# Mother_Board_Connectors.net
KiCad netlist of a schematic drawn in Altium Designer
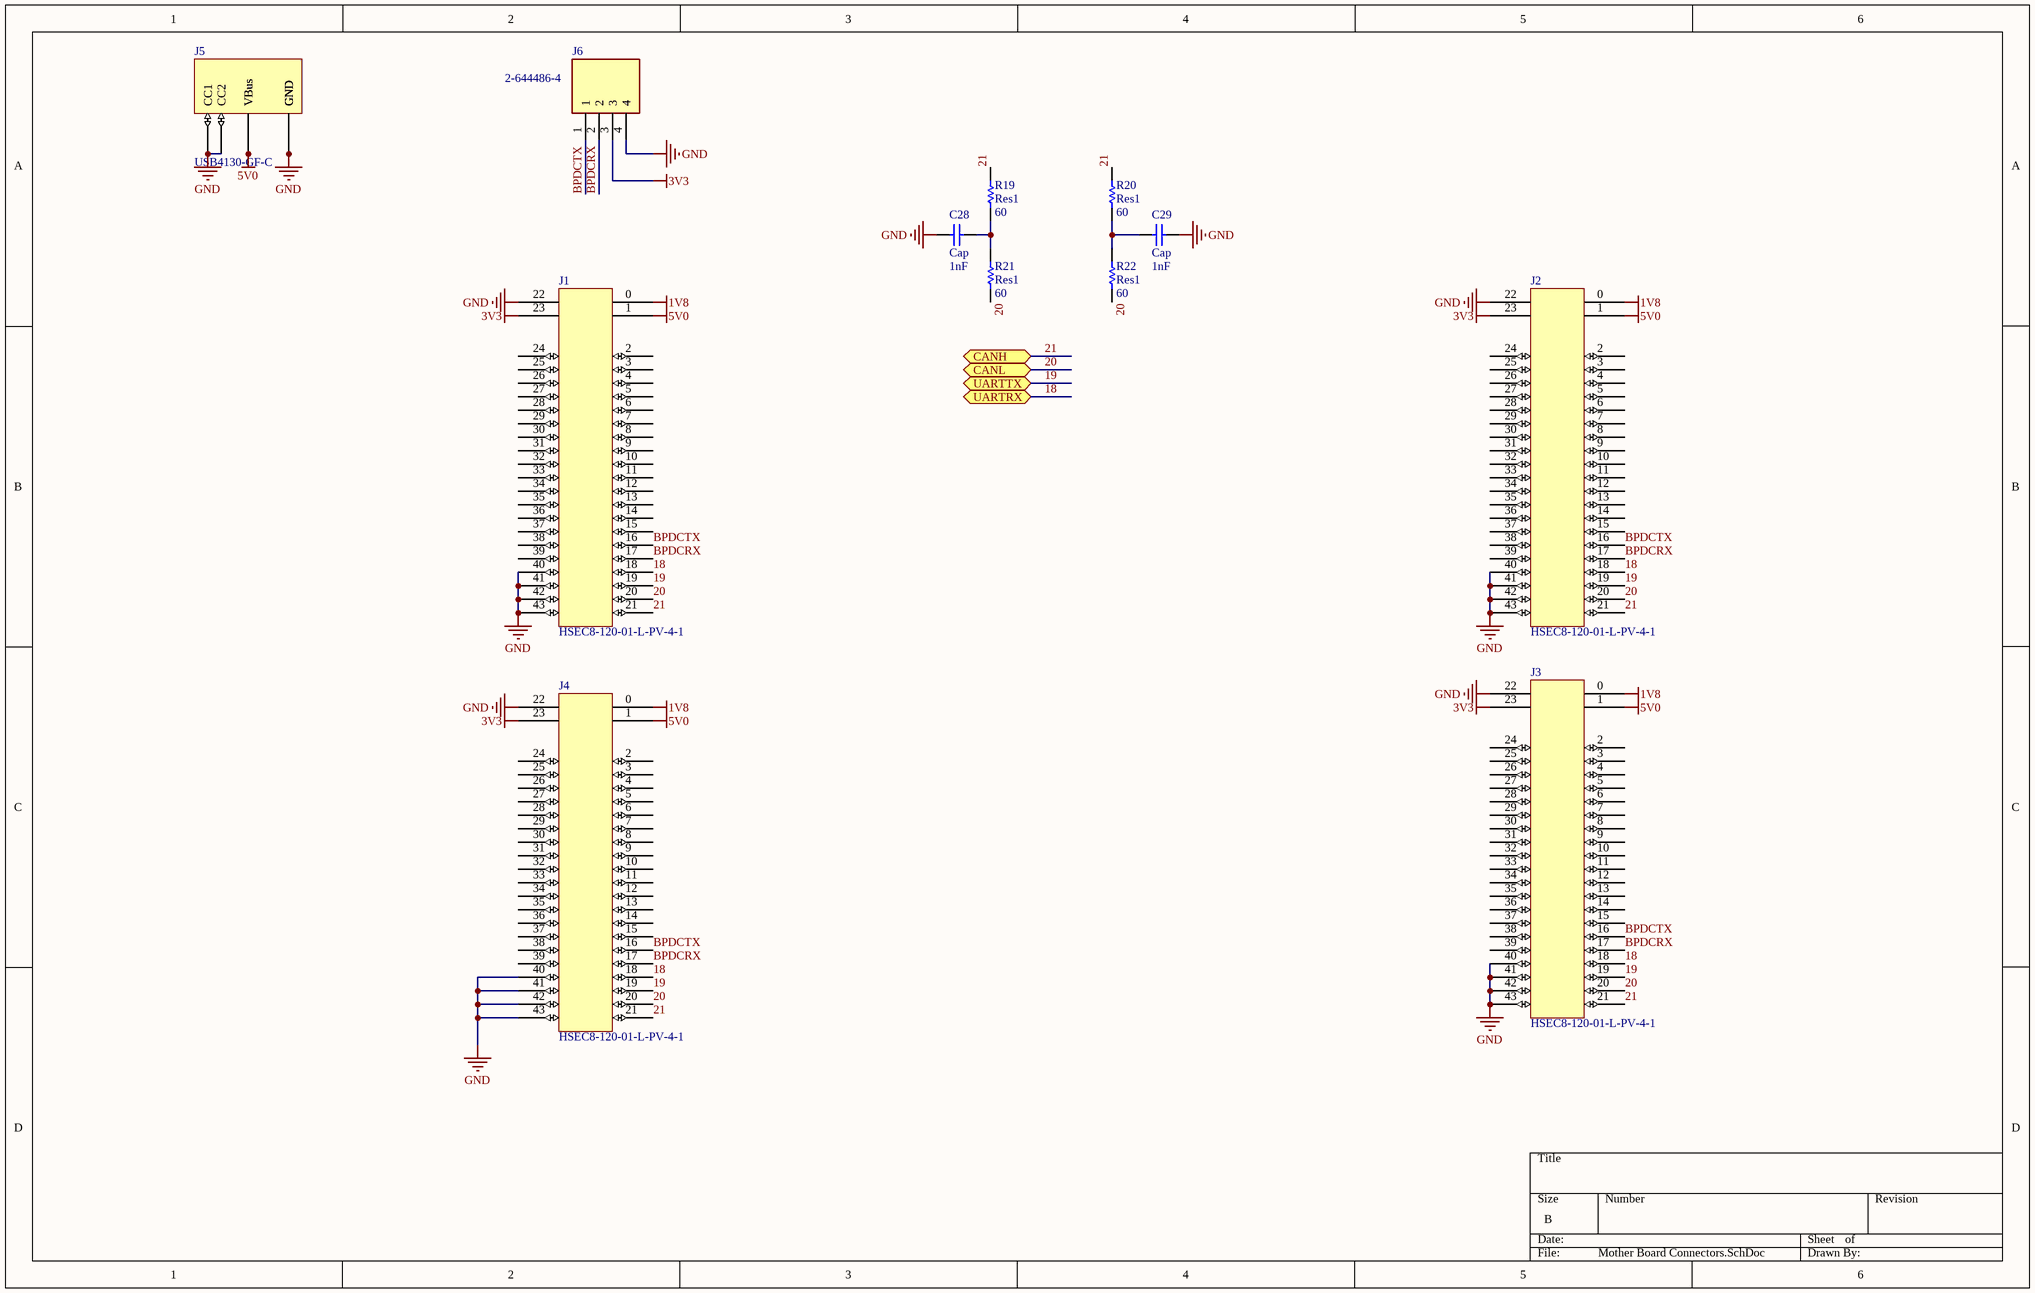
[diagram p0: Mother Board Connectors.SchDoc]

(export (version "E")
  (design (tool "Eeschema 10.0.6"))
  (components
    (comp (ref "C28")
      (value "Cap")
      (footprint "1608[0603]")
      (description "Capacitor")
      (fields (field (name "ALTIUM_VALUE") "1nF") (field (name "PUBLISHER") "Altium Limited"))
      (libsource (lib "Miscellaneous Devices") (part "Cap"))
    )
    (comp (ref "C29")
      (value "Cap")
      (footprint "1608[0603]")
      (description "Capacitor")
      (fields (field (name "ALTIUM_VALUE") "1nF") (field (name "PUBLISHER") "Altium Limited"))
      (libsource (lib "Miscellaneous Devices") (part "Cap"))
    )
    (comp (ref "J1")
      (value "HSEC8-120-01-L-PV-4-1")
      (footprint "HSEC8-120-01-L-PV-4-1")
      (libsource (lib "Edge Connector") (part "HSEC8-120-01-L-PV-4-1"))
    )
    (comp (ref "J2")
      (value "HSEC8-120-01-L-PV-4-1")
      (footprint "HSEC8-120-01-L-PV-4-1")
      (libsource (lib "Edge Connector") (part "HSEC8-120-01-L-PV-4-1"))
    )
    (comp (ref "J3")
      (value "HSEC8-120-01-L-PV-4-1")
      (footprint "HSEC8-120-01-L-PV-4-1")
      (libsource (lib "Edge Connector") (part "HSEC8-120-01-L-PV-4-1"))
    )
    (comp (ref "J4")
      (value "HSEC8-120-01-L-PV-4-1")
      (footprint "HSEC8-120-01-L-PV-4-1")
      (libsource (lib "Edge Connector") (part "HSEC8-120-01-L-PV-4-1"))
    )
    (comp (ref "J5")
      (value "USB4130-GF-C")
      (footprint "USB4130-GF-C")
      (libsource (lib "USB4130-GF-C") (part "USB4130-GF-C"))
    )
    (comp (ref "J6")
      (value "2-644486-4")
      (footprint "26444864")
      (description "Connector")
      (fields (field (name "MOUSER PART NUMBER") "571-2-644486-4"))
      (libsource (lib "SamacSys") (part "2-644486-4"))
    )
    (comp (ref "R19")
      (value "Res1")
      (footprint "0402-A")
      (description "Resistor")
      (fields (field (name "ALTIUM_VALUE") "60") (field (name "PUBLISHER") "Altium Limited"))
      (libsource (lib "Miscellaneous Devices") (part "Res1"))
    )
    (comp (ref "R20")
      (value "Res1")
      (footprint "0402-A")
      (description "Resistor")
      (fields (field (name "ALTIUM_VALUE") "60") (field (name "PUBLISHER") "Altium Limited"))
      (libsource (lib "Miscellaneous Devices") (part "Res1"))
    )
    (comp (ref "R21")
      (value "Res1")
      (footprint "0402-A")
      (description "Resistor")
      (fields (field (name "ALTIUM_VALUE") "60") (field (name "PUBLISHER") "Altium Limited"))
      (libsource (lib "Miscellaneous Devices") (part "Res1"))
    )
    (comp (ref "R22")
      (value "Res1")
      (footprint "0402-A")
      (description "Resistor")
      (fields (field (name "ALTIUM_VALUE") "60") (field (name "PUBLISHER") "Altium Limited"))
      (libsource (lib "Miscellaneous Devices") (part "Res1"))
    )
  )
  (nets
    (net (code "1") (name "/18") (class "Default")
      (node (ref "J1") (pin "18") (pinfunction "0_18") (pintype "bidirectional"))
      (node (ref "J2") (pin "18") (pinfunction "0_18") (pintype "bidirectional"))
      (node (ref "J3") (pin "18") (pinfunction "0_18") (pintype "bidirectional"))
      (node (ref "J4") (pin "18") (pinfunction "0_18") (pintype "bidirectional"))
    )
    (net (code "2") (name "/19") (class "Default")
      (node (ref "J1") (pin "19") (pinfunction "0_19") (pintype "bidirectional"))
      (node (ref "J2") (pin "19") (pinfunction "0_19") (pintype "bidirectional"))
      (node (ref "J3") (pin "19") (pinfunction "0_19") (pintype "bidirectional"))
      (node (ref "J4") (pin "19") (pinfunction "0_19") (pintype "bidirectional"))
    )
    (net (code "3") (name "/20") (class "Default")
      (node (ref "J1") (pin "20") (pinfunction "0_20") (pintype "bidirectional"))
      (node (ref "J2") (pin "20") (pinfunction "0_20") (pintype "bidirectional"))
      (node (ref "J3") (pin "20") (pinfunction "0_20") (pintype "bidirectional"))
      (node (ref "J4") (pin "20") (pinfunction "0_20") (pintype "bidirectional"))
      (node (ref "R21") (pin "1") (pinfunction "1_1") (pintype "passive"))
      (node (ref "R22") (pin "1") (pinfunction "1_1") (pintype "passive"))
    )
    (net (code "4") (name "/21") (class "Default")
      (node (ref "J1") (pin "21") (pinfunction "0_21") (pintype "bidirectional"))
      (node (ref "J2") (pin "21") (pinfunction "0_21") (pintype "bidirectional"))
      (node (ref "J3") (pin "21") (pinfunction "0_21") (pintype "bidirectional"))
      (node (ref "J4") (pin "21") (pinfunction "0_21") (pintype "bidirectional"))
      (node (ref "R19") (pin "2") (pinfunction "2_2") (pintype "passive"))
      (node (ref "R20") (pin "2") (pinfunction "2_2") (pintype "passive"))
    )
    (net (code "5") (name "/BPDCRX") (class "Default")
      (node (ref "J1") (pin "17") (pinfunction "0_17") (pintype "bidirectional"))
      (node (ref "J2") (pin "17") (pinfunction "0_17") (pintype "bidirectional"))
      (node (ref "J3") (pin "17") (pinfunction "0_17") (pintype "bidirectional"))
      (node (ref "J4") (pin "17") (pinfunction "0_17") (pintype "bidirectional"))
      (node (ref "J6") (pin "2") (pinfunction "2_2") (pintype "passive"))
    )
    (net (code "6") (name "/BPDCTX") (class "Default")
      (node (ref "J1") (pin "16") (pinfunction "0_16") (pintype "bidirectional"))
      (node (ref "J2") (pin "16") (pinfunction "0_16") (pintype "bidirectional"))
      (node (ref "J3") (pin "16") (pinfunction "0_16") (pintype "bidirectional"))
      (node (ref "J4") (pin "16") (pinfunction "0_16") (pintype "bidirectional"))
      (node (ref "J6") (pin "1") (pinfunction "1_1") (pintype "passive"))
    )
    (net (code "7") (name "1V8") (class "Default")
      (node (ref "J1") (pin "0") (pinfunction "0_0") (pintype "power_in"))
      (node (ref "J2") (pin "0") (pinfunction "0_0") (pintype "power_in"))
      (node (ref "J3") (pin "0") (pinfunction "0_0") (pintype "power_in"))
      (node (ref "J4") (pin "0") (pinfunction "0_0") (pintype "power_in"))
    )
    (net (code "8") (name "3V3") (class "Default")
      (node (ref "J1") (pin "23") (pinfunction "23_23") (pintype "power_in"))
      (node (ref "J2") (pin "23") (pinfunction "23_23") (pintype "power_in"))
      (node (ref "J3") (pin "23") (pinfunction "23_23") (pintype "power_in"))
      (node (ref "J4") (pin "23") (pinfunction "23_23") (pintype "power_in"))
      (node (ref "J6") (pin "3") (pinfunction "3_3") (pintype "passive"))
    )
    (net (code "9") (name "5V0") (class "Default")
      (node (ref "J1") (pin "1") (pinfunction "0_1") (pintype "power_in"))
      (node (ref "J2") (pin "1") (pinfunction "0_1") (pintype "power_in"))
      (node (ref "J3") (pin "1") (pinfunction "0_1") (pintype "power_in"))
      (node (ref "J4") (pin "1") (pinfunction "0_1") (pintype "power_in"))
      (node (ref "J5") (pin "2") (pinfunction "VBus_2") (pintype "power_in"))
      (node (ref "J5") (pin "5") (pinfunction "VBus_5") (pintype "power_in"))
    )
    (net (code "10") (name "GND") (class "Default")
      (node (ref "C28") (pin "2") (pinfunction "2_2") (pintype "passive"))
      (node (ref "C29") (pin "1") (pinfunction "1_1") (pintype "passive"))
      (node (ref "J1") (pin "22") (pinfunction "0_22") (pintype "power_in"))
      (node (ref "J1") (pin "40") (pinfunction "40_40") (pintype "bidirectional"))
      (node (ref "J1") (pin "41") (pinfunction "41_41") (pintype "bidirectional"))
      (node (ref "J1") (pin "42") (pinfunction "42_42") (pintype "bidirectional"))
      (node (ref "J1") (pin "43") (pinfunction "43_43") (pintype "bidirectional"))
      (node (ref "J2") (pin "22") (pinfunction "0_22") (pintype "power_in"))
      (node (ref "J2") (pin "40") (pinfunction "40_40") (pintype "bidirectional"))
      (node (ref "J2") (pin "41") (pinfunction "41_41") (pintype "bidirectional"))
      (node (ref "J2") (pin "42") (pinfunction "42_42") (pintype "bidirectional"))
      (node (ref "J2") (pin "43") (pinfunction "43_43") (pintype "bidirectional"))
      (node (ref "J3") (pin "22") (pinfunction "0_22") (pintype "power_in"))
      (node (ref "J3") (pin "40") (pinfunction "40_40") (pintype "bidirectional"))
      (node (ref "J3") (pin "41") (pinfunction "41_41") (pintype "bidirectional"))
      (node (ref "J3") (pin "42") (pinfunction "42_42") (pintype "bidirectional"))
      (node (ref "J3") (pin "43") (pinfunction "43_43") (pintype "bidirectional"))
      (node (ref "J4") (pin "22") (pinfunction "0_22") (pintype "power_in"))
      (node (ref "J4") (pin "40") (pinfunction "40_40") (pintype "bidirectional"))
      (node (ref "J4") (pin "41") (pinfunction "41_41") (pintype "bidirectional"))
      (node (ref "J4") (pin "42") (pinfunction "42_42") (pintype "bidirectional"))
      (node (ref "J4") (pin "43") (pinfunction "43_43") (pintype "bidirectional"))
      (node (ref "J5") (pin "1") (pinfunction "GND_1") (pintype "power_in"))
      (node (ref "J5") (pin "3") (pinfunction "CC1_3") (pintype "bidirectional"))
      (node (ref "J5") (pin "4") (pinfunction "CC2_4") (pintype "bidirectional"))
      (node (ref "J5") (pin "6") (pinfunction "GND_6") (pintype "power_in"))
      (node (ref "J5") (pin "7") (pinfunction "GND_7") (pintype "power_in"))
      (node (ref "J5") (pin "8") (pinfunction "GND_8") (pintype "power_in"))
      (node (ref "J6") (pin "4") (pinfunction "4_4") (pintype "passive"))
    )
    (net (code "11") (name "Net-(C28-Pad1)") (class "Default")
      (node (ref "C28") (pin "1") (pinfunction "1_1") (pintype "passive"))
      (node (ref "R19") (pin "1") (pinfunction "1_1") (pintype "passive"))
      (node (ref "R21") (pin "2") (pinfunction "2_2") (pintype "passive"))
    )
    (net (code "12") (name "Net-(C29-Pad2)") (class "Default")
      (node (ref "C29") (pin "2") (pinfunction "2_2") (pintype "passive"))
      (node (ref "R20") (pin "1") (pinfunction "1_1") (pintype "passive"))
      (node (ref "R22") (pin "2") (pinfunction "2_2") (pintype "passive"))
    )
    (net (code "13") (name "unconnected-(J1-0-Pad2)") (class "Default")
      (node (ref "J1") (pin "2") (pinfunction "0_2") (pintype "bidirectional"))
    )
    (net (code "14") (name "unconnected-(J1-0-Pad3)") (class "Default")
      (node (ref "J1") (pin "3") (pinfunction "0_3") (pintype "bidirectional"))
    )
    (net (code "15") (name "unconnected-(J1-0-Pad4)") (class "Default")
      (node (ref "J1") (pin "4") (pinfunction "0_4") (pintype "bidirectional"))
    )
    (net (code "16") (name "unconnected-(J1-0-Pad5)") (class "Default")
      (node (ref "J1") (pin "5") (pinfunction "0_5") (pintype "bidirectional"))
    )
    (net (code "17") (name "unconnected-(J1-0-Pad6)") (class "Default")
      (node (ref "J1") (pin "6") (pinfunction "0_6") (pintype "bidirectional"))
    )
    (net (code "18") (name "unconnected-(J1-0-Pad7)") (class "Default")
      (node (ref "J1") (pin "7") (pinfunction "0_7") (pintype "bidirectional"))
    )
    (net (code "19") (name "unconnected-(J1-0-Pad8)") (class "Default")
      (node (ref "J1") (pin "8") (pinfunction "0_8") (pintype "bidirectional"))
    )
    (net (code "20") (name "unconnected-(J1-0-Pad9)") (class "Default")
      (node (ref "J1") (pin "9") (pinfunction "0_9") (pintype "bidirectional"))
    )
    (net (code "21") (name "unconnected-(J1-0-Pad10)") (class "Default")
      (node (ref "J1") (pin "10") (pinfunction "0_10") (pintype "bidirectional"))
    )
    (net (code "22") (name "unconnected-(J1-0-Pad11)") (class "Default")
      (node (ref "J1") (pin "11") (pinfunction "0_11") (pintype "bidirectional"))
    )
    (net (code "23") (name "unconnected-(J1-0-Pad12)") (class "Default")
      (node (ref "J1") (pin "12") (pinfunction "0_12") (pintype "bidirectional"))
    )
    (net (code "24") (name "unconnected-(J1-0-Pad13)") (class "Default")
      (node (ref "J1") (pin "13") (pinfunction "0_13") (pintype "bidirectional"))
    )
    (net (code "25") (name "unconnected-(J1-0-Pad14)") (class "Default")
      (node (ref "J1") (pin "14") (pinfunction "0_14") (pintype "bidirectional"))
    )
    (net (code "26") (name "unconnected-(J1-0-Pad15)") (class "Default")
      (node (ref "J1") (pin "15") (pinfunction "0_15") (pintype "bidirectional"))
    )
    (net (code "27") (name "unconnected-(J1-Pad24)") (class "Default")
      (node (ref "J1") (pin "24") (pinfunction "24_24") (pintype "bidirectional"))
    )
    (net (code "28") (name "unconnected-(J1-Pad25)") (class "Default")
      (node (ref "J1") (pin "25") (pinfunction "25_25") (pintype "bidirectional"))
    )
    (net (code "29") (name "unconnected-(J1-Pad26)") (class "Default")
      (node (ref "J1") (pin "26") (pinfunction "26_26") (pintype "bidirectional"))
    )
    (net (code "30") (name "unconnected-(J1-Pad27)") (class "Default")
      (node (ref "J1") (pin "27") (pinfunction "27_27") (pintype "bidirectional"))
    )
    (net (code "31") (name "unconnected-(J1-Pad28)") (class "Default")
      (node (ref "J1") (pin "28") (pinfunction "28_28") (pintype "bidirectional"))
    )
    (net (code "32") (name "unconnected-(J1-Pad29)") (class "Default")
      (node (ref "J1") (pin "29") (pinfunction "29_29") (pintype "bidirectional"))
    )
    (net (code "33") (name "unconnected-(J1-Pad30)") (class "Default")
      (node (ref "J1") (pin "30") (pinfunction "30_30") (pintype "bidirectional"))
    )
    (net (code "34") (name "unconnected-(J1-Pad31)") (class "Default")
      (node (ref "J1") (pin "31") (pinfunction "31_31") (pintype "bidirectional"))
    )
    (net (code "35") (name "unconnected-(J1-Pad32)") (class "Default")
      (node (ref "J1") (pin "32") (pinfunction "32_32") (pintype "bidirectional"))
    )
    (net (code "36") (name "unconnected-(J1-Pad33)") (class "Default")
      (node (ref "J1") (pin "33") (pinfunction "33_33") (pintype "bidirectional"))
    )
    (net (code "37") (name "unconnected-(J1-Pad34)") (class "Default")
      (node (ref "J1") (pin "34") (pinfunction "34_34") (pintype "bidirectional"))
    )
    (net (code "38") (name "unconnected-(J1-Pad35)") (class "Default")
      (node (ref "J1") (pin "35") (pinfunction "35_35") (pintype "bidirectional"))
    )
    (net (code "39") (name "unconnected-(J1-Pad36)") (class "Default")
      (node (ref "J1") (pin "36") (pinfunction "36_36") (pintype "bidirectional"))
    )
    (net (code "40") (name "unconnected-(J1-Pad37)") (class "Default")
      (node (ref "J1") (pin "37") (pinfunction "37_37") (pintype "bidirectional"))
    )
    (net (code "41") (name "unconnected-(J1-Pad38)") (class "Default")
      (node (ref "J1") (pin "38") (pinfunction "38_38") (pintype "bidirectional"))
    )
    (net (code "42") (name "unconnected-(J1-Pad39)") (class "Default")
      (node (ref "J1") (pin "39") (pinfunction "39_39") (pintype "bidirectional"))
    )
    (net (code "43") (name "unconnected-(J2-0-Pad2)") (class "Default")
      (node (ref "J2") (pin "2") (pinfunction "0_2") (pintype "bidirectional"))
    )
    (net (code "44") (name "unconnected-(J2-0-Pad3)") (class "Default")
      (node (ref "J2") (pin "3") (pinfunction "0_3") (pintype "bidirectional"))
    )
    (net (code "45") (name "unconnected-(J2-0-Pad4)") (class "Default")
      (node (ref "J2") (pin "4") (pinfunction "0_4") (pintype "bidirectional"))
    )
    (net (code "46") (name "unconnected-(J2-0-Pad5)") (class "Default")
      (node (ref "J2") (pin "5") (pinfunction "0_5") (pintype "bidirectional"))
    )
    (net (code "47") (name "unconnected-(J2-0-Pad6)") (class "Default")
      (node (ref "J2") (pin "6") (pinfunction "0_6") (pintype "bidirectional"))
    )
    (net (code "48") (name "unconnected-(J2-0-Pad7)") (class "Default")
      (node (ref "J2") (pin "7") (pinfunction "0_7") (pintype "bidirectional"))
    )
    (net (code "49") (name "unconnected-(J2-0-Pad8)") (class "Default")
      (node (ref "J2") (pin "8") (pinfunction "0_8") (pintype "bidirectional"))
    )
    (net (code "50") (name "unconnected-(J2-0-Pad9)") (class "Default")
      (node (ref "J2") (pin "9") (pinfunction "0_9") (pintype "bidirectional"))
    )
    (net (code "51") (name "unconnected-(J2-0-Pad10)") (class "Default")
      (node (ref "J2") (pin "10") (pinfunction "0_10") (pintype "bidirectional"))
    )
    (net (code "52") (name "unconnected-(J2-0-Pad11)") (class "Default")
      (node (ref "J2") (pin "11") (pinfunction "0_11") (pintype "bidirectional"))
    )
    (net (code "53") (name "unconnected-(J2-0-Pad12)") (class "Default")
      (node (ref "J2") (pin "12") (pinfunction "0_12") (pintype "bidirectional"))
    )
    (net (code "54") (name "unconnected-(J2-0-Pad13)") (class "Default")
      (node (ref "J2") (pin "13") (pinfunction "0_13") (pintype "bidirectional"))
    )
    (net (code "55") (name "unconnected-(J2-0-Pad14)") (class "Default")
      (node (ref "J2") (pin "14") (pinfunction "0_14") (pintype "bidirectional"))
    )
    (net (code "56") (name "unconnected-(J2-0-Pad15)") (class "Default")
      (node (ref "J2") (pin "15") (pinfunction "0_15") (pintype "bidirectional"))
    )
    (net (code "57") (name "unconnected-(J2-Pad24)") (class "Default")
      (node (ref "J2") (pin "24") (pinfunction "24_24") (pintype "bidirectional"))
    )
    (net (code "58") (name "unconnected-(J2-Pad25)") (class "Default")
      (node (ref "J2") (pin "25") (pinfunction "25_25") (pintype "bidirectional"))
    )
    (net (code "59") (name "unconnected-(J2-Pad26)") (class "Default")
      (node (ref "J2") (pin "26") (pinfunction "26_26") (pintype "bidirectional"))
    )
    (net (code "60") (name "unconnected-(J2-Pad27)") (class "Default")
      (node (ref "J2") (pin "27") (pinfunction "27_27") (pintype "bidirectional"))
    )
    (net (code "61") (name "unconnected-(J2-Pad28)") (class "Default")
      (node (ref "J2") (pin "28") (pinfunction "28_28") (pintype "bidirectional"))
    )
    (net (code "62") (name "unconnected-(J2-Pad29)") (class "Default")
      (node (ref "J2") (pin "29") (pinfunction "29_29") (pintype "bidirectional"))
    )
    (net (code "63") (name "unconnected-(J2-Pad30)") (class "Default")
      (node (ref "J2") (pin "30") (pinfunction "30_30") (pintype "bidirectional"))
    )
    (net (code "64") (name "unconnected-(J2-Pad31)") (class "Default")
      (node (ref "J2") (pin "31") (pinfunction "31_31") (pintype "bidirectional"))
    )
    (net (code "65") (name "unconnected-(J2-Pad32)") (class "Default")
      (node (ref "J2") (pin "32") (pinfunction "32_32") (pintype "bidirectional"))
    )
    (net (code "66") (name "unconnected-(J2-Pad33)") (class "Default")
      (node (ref "J2") (pin "33") (pinfunction "33_33") (pintype "bidirectional"))
    )
    (net (code "67") (name "unconnected-(J2-Pad34)") (class "Default")
      (node (ref "J2") (pin "34") (pinfunction "34_34") (pintype "bidirectional"))
    )
    (net (code "68") (name "unconnected-(J2-Pad35)") (class "Default")
      (node (ref "J2") (pin "35") (pinfunction "35_35") (pintype "bidirectional"))
    )
    (net (code "69") (name "unconnected-(J2-Pad36)") (class "Default")
      (node (ref "J2") (pin "36") (pinfunction "36_36") (pintype "bidirectional"))
    )
    (net (code "70") (name "unconnected-(J2-Pad37)") (class "Default")
      (node (ref "J2") (pin "37") (pinfunction "37_37") (pintype "bidirectional"))
    )
    (net (code "71") (name "unconnected-(J2-Pad38)") (class "Default")
      (node (ref "J2") (pin "38") (pinfunction "38_38") (pintype "bidirectional"))
    )
    (net (code "72") (name "unconnected-(J2-Pad39)") (class "Default")
      (node (ref "J2") (pin "39") (pinfunction "39_39") (pintype "bidirectional"))
    )
    (net (code "73") (name "unconnected-(J3-0-Pad2)") (class "Default")
      (node (ref "J3") (pin "2") (pinfunction "0_2") (pintype "bidirectional"))
    )
    (net (code "74") (name "unconnected-(J3-0-Pad3)") (class "Default")
      (node (ref "J3") (pin "3") (pinfunction "0_3") (pintype "bidirectional"))
    )
    (net (code "75") (name "unconnected-(J3-0-Pad4)") (class "Default")
      (node (ref "J3") (pin "4") (pinfunction "0_4") (pintype "bidirectional"))
    )
    (net (code "76") (name "unconnected-(J3-0-Pad5)") (class "Default")
      (node (ref "J3") (pin "5") (pinfunction "0_5") (pintype "bidirectional"))
    )
    (net (code "77") (name "unconnected-(J3-0-Pad6)") (class "Default")
      (node (ref "J3") (pin "6") (pinfunction "0_6") (pintype "bidirectional"))
    )
    (net (code "78") (name "unconnected-(J3-0-Pad7)") (class "Default")
      (node (ref "J3") (pin "7") (pinfunction "0_7") (pintype "bidirectional"))
    )
    (net (code "79") (name "unconnected-(J3-0-Pad8)") (class "Default")
      (node (ref "J3") (pin "8") (pinfunction "0_8") (pintype "bidirectional"))
    )
    (net (code "80") (name "unconnected-(J3-0-Pad9)") (class "Default")
      (node (ref "J3") (pin "9") (pinfunction "0_9") (pintype "bidirectional"))
    )
    (net (code "81") (name "unconnected-(J3-0-Pad10)") (class "Default")
      (node (ref "J3") (pin "10") (pinfunction "0_10") (pintype "bidirectional"))
    )
    (net (code "82") (name "unconnected-(J3-0-Pad11)") (class "Default")
      (node (ref "J3") (pin "11") (pinfunction "0_11") (pintype "bidirectional"))
    )
    (net (code "83") (name "unconnected-(J3-0-Pad12)") (class "Default")
      (node (ref "J3") (pin "12") (pinfunction "0_12") (pintype "bidirectional"))
    )
    (net (code "84") (name "unconnected-(J3-0-Pad13)") (class "Default")
      (node (ref "J3") (pin "13") (pinfunction "0_13") (pintype "bidirectional"))
    )
    (net (code "85") (name "unconnected-(J3-0-Pad14)") (class "Default")
      (node (ref "J3") (pin "14") (pinfunction "0_14") (pintype "bidirectional"))
    )
    (net (code "86") (name "unconnected-(J3-0-Pad15)") (class "Default")
      (node (ref "J3") (pin "15") (pinfunction "0_15") (pintype "bidirectional"))
    )
    (net (code "87") (name "unconnected-(J3-Pad24)") (class "Default")
      (node (ref "J3") (pin "24") (pinfunction "24_24") (pintype "bidirectional"))
    )
    (net (code "88") (name "unconnected-(J3-Pad25)") (class "Default")
      (node (ref "J3") (pin "25") (pinfunction "25_25") (pintype "bidirectional"))
    )
    (net (code "89") (name "unconnected-(J3-Pad26)") (class "Default")
      (node (ref "J3") (pin "26") (pinfunction "26_26") (pintype "bidirectional"))
    )
    (net (code "90") (name "unconnected-(J3-Pad27)") (class "Default")
      (node (ref "J3") (pin "27") (pinfunction "27_27") (pintype "bidirectional"))
    )
    (net (code "91") (name "unconnected-(J3-Pad28)") (class "Default")
      (node (ref "J3") (pin "28") (pinfunction "28_28") (pintype "bidirectional"))
    )
    (net (code "92") (name "unconnected-(J3-Pad29)") (class "Default")
      (node (ref "J3") (pin "29") (pinfunction "29_29") (pintype "bidirectional"))
    )
    (net (code "93") (name "unconnected-(J3-Pad30)") (class "Default")
      (node (ref "J3") (pin "30") (pinfunction "30_30") (pintype "bidirectional"))
    )
    (net (code "94") (name "unconnected-(J3-Pad31)") (class "Default")
      (node (ref "J3") (pin "31") (pinfunction "31_31") (pintype "bidirectional"))
    )
    (net (code "95") (name "unconnected-(J3-Pad32)") (class "Default")
      (node (ref "J3") (pin "32") (pinfunction "32_32") (pintype "bidirectional"))
    )
    (net (code "96") (name "unconnected-(J3-Pad33)") (class "Default")
      (node (ref "J3") (pin "33") (pinfunction "33_33") (pintype "bidirectional"))
    )
    (net (code "97") (name "unconnected-(J3-Pad34)") (class "Default")
      (node (ref "J3") (pin "34") (pinfunction "34_34") (pintype "bidirectional"))
    )
    (net (code "98") (name "unconnected-(J3-Pad35)") (class "Default")
      (node (ref "J3") (pin "35") (pinfunction "35_35") (pintype "bidirectional"))
    )
    (net (code "99") (name "unconnected-(J3-Pad36)") (class "Default")
      (node (ref "J3") (pin "36") (pinfunction "36_36") (pintype "bidirectional"))
    )
    (net (code "100") (name "unconnected-(J3-Pad37)") (class "Default")
      (node (ref "J3") (pin "37") (pinfunction "37_37") (pintype "bidirectional"))
    )
    (net (code "101") (name "unconnected-(J3-Pad38)") (class "Default")
      (node (ref "J3") (pin "38") (pinfunction "38_38") (pintype "bidirectional"))
    )
    (net (code "102") (name "unconnected-(J3-Pad39)") (class "Default")
      (node (ref "J3") (pin "39") (pinfunction "39_39") (pintype "bidirectional"))
    )
    (net (code "103") (name "unconnected-(J4-0-Pad2)") (class "Default")
      (node (ref "J4") (pin "2") (pinfunction "0_2") (pintype "bidirectional"))
    )
    (net (code "104") (name "unconnected-(J4-0-Pad3)") (class "Default")
      (node (ref "J4") (pin "3") (pinfunction "0_3") (pintype "bidirectional"))
    )
    (net (code "105") (name "unconnected-(J4-0-Pad4)") (class "Default")
      (node (ref "J4") (pin "4") (pinfunction "0_4") (pintype "bidirectional"))
    )
    (net (code "106") (name "unconnected-(J4-0-Pad5)") (class "Default")
      (node (ref "J4") (pin "5") (pinfunction "0_5") (pintype "bidirectional"))
    )
    (net (code "107") (name "unconnected-(J4-0-Pad6)") (class "Default")
      (node (ref "J4") (pin "6") (pinfunction "0_6") (pintype "bidirectional"))
    )
    (net (code "108") (name "unconnected-(J4-0-Pad7)") (class "Default")
      (node (ref "J4") (pin "7") (pinfunction "0_7") (pintype "bidirectional"))
    )
    (net (code "109") (name "unconnected-(J4-0-Pad8)") (class "Default")
      (node (ref "J4") (pin "8") (pinfunction "0_8") (pintype "bidirectional"))
    )
    (net (code "110") (name "unconnected-(J4-0-Pad9)") (class "Default")
      (node (ref "J4") (pin "9") (pinfunction "0_9") (pintype "bidirectional"))
    )
    (net (code "111") (name "unconnected-(J4-0-Pad10)") (class "Default")
      (node (ref "J4") (pin "10") (pinfunction "0_10") (pintype "bidirectional"))
    )
    (net (code "112") (name "unconnected-(J4-0-Pad11)") (class "Default")
      (node (ref "J4") (pin "11") (pinfunction "0_11") (pintype "bidirectional"))
    )
    (net (code "113") (name "unconnected-(J4-0-Pad12)") (class "Default")
      (node (ref "J4") (pin "12") (pinfunction "0_12") (pintype "bidirectional"))
    )
    (net (code "114") (name "unconnected-(J4-0-Pad13)") (class "Default")
      (node (ref "J4") (pin "13") (pinfunction "0_13") (pintype "bidirectional"))
    )
    (net (code "115") (name "unconnected-(J4-0-Pad14)") (class "Default")
      (node (ref "J4") (pin "14") (pinfunction "0_14") (pintype "bidirectional"))
    )
    (net (code "116") (name "unconnected-(J4-0-Pad15)") (class "Default")
      (node (ref "J4") (pin "15") (pinfunction "0_15") (pintype "bidirectional"))
    )
    (net (code "117") (name "unconnected-(J4-Pad24)") (class "Default")
      (node (ref "J4") (pin "24") (pinfunction "24_24") (pintype "bidirectional"))
    )
    (net (code "118") (name "unconnected-(J4-Pad25)") (class "Default")
      (node (ref "J4") (pin "25") (pinfunction "25_25") (pintype "bidirectional"))
    )
    (net (code "119") (name "unconnected-(J4-Pad26)") (class "Default")
      (node (ref "J4") (pin "26") (pinfunction "26_26") (pintype "bidirectional"))
    )
    (net (code "120") (name "unconnected-(J4-Pad27)") (class "Default")
      (node (ref "J4") (pin "27") (pinfunction "27_27") (pintype "bidirectional"))
    )
    (net (code "121") (name "unconnected-(J4-Pad28)") (class "Default")
      (node (ref "J4") (pin "28") (pinfunction "28_28") (pintype "bidirectional"))
    )
    (net (code "122") (name "unconnected-(J4-Pad29)") (class "Default")
      (node (ref "J4") (pin "29") (pinfunction "29_29") (pintype "bidirectional"))
    )
    (net (code "123") (name "unconnected-(J4-Pad30)") (class "Default")
      (node (ref "J4") (pin "30") (pinfunction "30_30") (pintype "bidirectional"))
    )
    (net (code "124") (name "unconnected-(J4-Pad31)") (class "Default")
      (node (ref "J4") (pin "31") (pinfunction "31_31") (pintype "bidirectional"))
    )
    (net (code "125") (name "unconnected-(J4-Pad32)") (class "Default")
      (node (ref "J4") (pin "32") (pinfunction "32_32") (pintype "bidirectional"))
    )
    (net (code "126") (name "unconnected-(J4-Pad33)") (class "Default")
      (node (ref "J4") (pin "33") (pinfunction "33_33") (pintype "bidirectional"))
    )
    (net (code "127") (name "unconnected-(J4-Pad34)") (class "Default")
      (node (ref "J4") (pin "34") (pinfunction "34_34") (pintype "bidirectional"))
    )
    (net (code "128") (name "unconnected-(J4-Pad35)") (class "Default")
      (node (ref "J4") (pin "35") (pinfunction "35_35") (pintype "bidirectional"))
    )
    (net (code "129") (name "unconnected-(J4-Pad36)") (class "Default")
      (node (ref "J4") (pin "36") (pinfunction "36_36") (pintype "bidirectional"))
    )
    (net (code "130") (name "unconnected-(J4-Pad37)") (class "Default")
      (node (ref "J4") (pin "37") (pinfunction "37_37") (pintype "bidirectional"))
    )
    (net (code "131") (name "unconnected-(J4-Pad38)") (class "Default")
      (node (ref "J4") (pin "38") (pinfunction "38_38") (pintype "bidirectional"))
    )
    (net (code "132") (name "unconnected-(J4-Pad39)") (class "Default")
      (node (ref "J4") (pin "39") (pinfunction "39_39") (pintype "bidirectional"))
    )
  )
)
